# Project_Milestone04.net
KiCad netlist of a schematic drawn in EAGLE
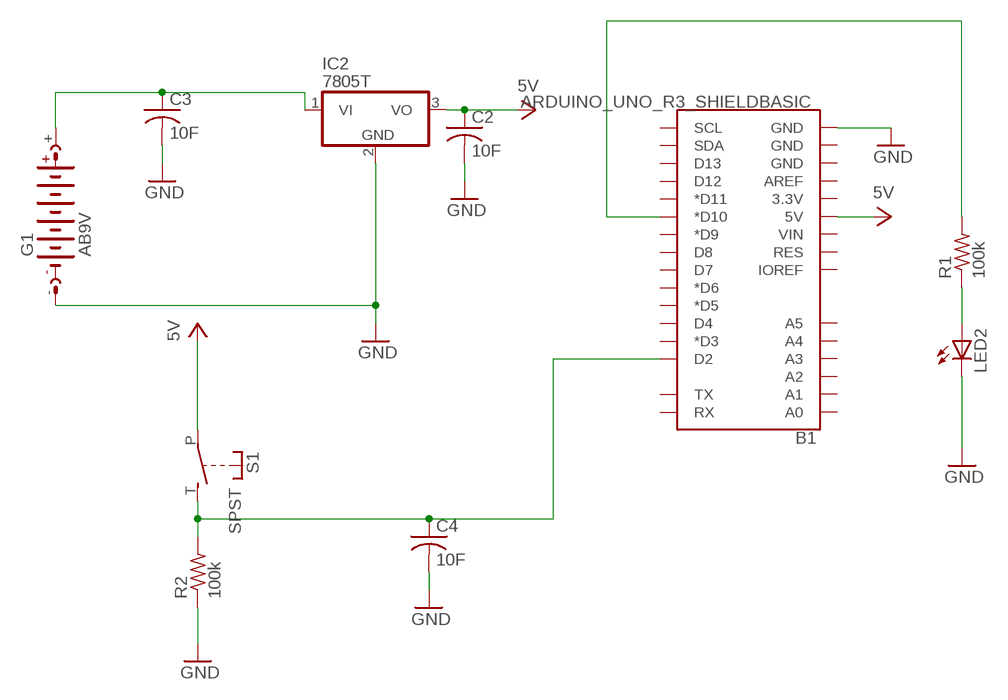
[diagram p0: schematic, sheet 1]

(export (version "E")
  (design (tool "Eeschema 10.0.6"))
  (components
    (comp (ref "B1")
      (value "ARDUINO_UNO_R3_SHIELDBASIC")
      (footprint "eagle-import:UNO_R3_SHIELD")
      (libsource (lib "eagle-import") (part "ARDUINO_UNO_R3_SHIELDBASIC"))
    )
    (comp (ref "C2")
      (value "10F")
      (footprint "eagle-import:C0805")
      (libsource (lib "eagle-import") (part "C-USC0805"))
    )
    (comp (ref "C3")
      (value "10F")
      (footprint "eagle-import:C0805")
      (libsource (lib "eagle-import") (part "C-USC0805"))
    )
    (comp (ref "C4")
      (value "10F")
      (footprint "eagle-import:C0805")
      (libsource (lib "eagle-import") (part "C-USC0805"))
    )
    (comp (ref "G1")
      (value "AB9V")
      (footprint "eagle-import:AB9V")
      (libsource (lib "eagle-import") (part "AB9V"))
    )
    (comp (ref "IC2")
      (value "7805T")
      (footprint "eagle-import:TO220H")
      (libsource (lib "eagle-import") (part "78T05"))
    )
    (comp (ref "LED2")
      (value "LED5MM")
      (footprint "eagle-import:LED5MM")
      (libsource (lib "eagle-import") (part "LED5MM"))
    )
    (comp (ref "R1")
      (value "100k")
      (footprint "eagle-import:0207_10")
      (libsource (lib "eagle-import") (part "R-US_0207/10"))
    )
    (comp (ref "R2")
      (value "100k")
      (footprint "eagle-import:0207_10")
      (libsource (lib "eagle-import") (part "R-US_0207/10"))
    )
    (comp (ref "S1")
      (value "SPST")
      (footprint "eagle-import:JUDCOSPST")
      (libsource (lib "eagle-import") (part "SPST"))
    )
  )
  (nets
    (net (code "1") (name "5V") (class "Default")
      (node (ref "B1") (pin "5V") (pinfunction "5V_5V") (pintype "bidirectional"))
      (node (ref "C2") (pin "1") (pinfunction "1_1") (pintype "passive"))
      (node (ref "IC2") (pin "3") (pinfunction "VO_3") (pintype "passive"))
      (node (ref "S1") (pin "P") (pinfunction "P_P") (pintype "passive"))
    )
    (net (code "2") (name "GND") (class "Default")
      (node (ref "B1") (pin "GND@0") (pinfunction "GND_GND@0") (pintype "bidirectional"))
      (node (ref "C2") (pin "2") (pinfunction "2_2") (pintype "passive"))
      (node (ref "C3") (pin "2") (pinfunction "2_2") (pintype "passive"))
      (node (ref "C4") (pin "2") (pinfunction "2_2") (pintype "passive"))
      (node (ref "G1") (pin "-") (pinfunction "-_-") (pintype "passive"))
      (node (ref "IC2") (pin "2") (pinfunction "GND_2") (pintype "passive"))
      (node (ref "LED2") (pin "K") (pinfunction "C_K") (pintype "passive"))
      (node (ref "R2") (pin "1") (pinfunction "1_1") (pintype "passive"))
    )
    (net (code "3") (name "Net-(B1-*D10)") (class "Default")
      (node (ref "B1") (pin "D10") (pinfunction "*D10_D10") (pintype "bidirectional"))
      (node (ref "R1") (pin "2") (pinfunction "2_2") (pintype "passive"))
    )
    (net (code "4") (name "Net-(IC2-VI)") (class "Default")
      (node (ref "C3") (pin "1") (pinfunction "1_1") (pintype "passive"))
      (node (ref "G1") (pin "+") (pinfunction "+_+") (pintype "passive"))
      (node (ref "IC2") (pin "1") (pinfunction "VI_1") (pintype "input"))
    )
    (net (code "5") (name "Net-(LED2-PadA)") (class "Default")
      (node (ref "LED2") (pin "A") (pinfunction "A_A") (pintype "passive"))
      (node (ref "R1") (pin "1") (pinfunction "1_1") (pintype "passive"))
    )
    (net (code "6") (name "Net-(S1-S)") (class "Default")
      (node (ref "B1") (pin "D2") (pinfunction "D2_D2") (pintype "bidirectional"))
      (node (ref "C4") (pin "1") (pinfunction "1_1") (pintype "passive"))
      (node (ref "R2") (pin "2") (pinfunction "2_2") (pintype "passive"))
      (node (ref "S1") (pin "T") (pinfunction "S_T") (pintype "passive"))
    )
    (net (code "7") (name "unconnected-(B1-*D3-PadD3)") (class "Default")
      (node (ref "B1") (pin "D3") (pinfunction "*D3_D3") (pintype "bidirectional"))
    )
    (net (code "8") (name "unconnected-(B1-*D5-PadD5)") (class "Default")
      (node (ref "B1") (pin "D5") (pinfunction "*D5_D5") (pintype "bidirectional"))
    )
    (net (code "9") (name "unconnected-(B1-*D6-PadD6)") (class "Default")
      (node (ref "B1") (pin "D6") (pinfunction "*D6_D6") (pintype "bidirectional"))
    )
    (net (code "10") (name "unconnected-(B1-*D9-PadD9)") (class "Default")
      (node (ref "B1") (pin "D9") (pinfunction "*D9_D9") (pintype "bidirectional"))
    )
    (net (code "11") (name "unconnected-(B1-*D11-PadD11)") (class "Default")
      (node (ref "B1") (pin "D11") (pinfunction "*D11_D11") (pintype "bidirectional"))
    )
    (net (code "12") (name "unconnected-(B1-GND-PadGND@1)") (class "Default")
      (node (ref "B1") (pin "GND@1") (pinfunction "GND_GND@1") (pintype "bidirectional"))
    )
    (net (code "13") (name "unconnected-(B1-GND-PadGND@2)") (class "Default")
      (node (ref "B1") (pin "GND@2") (pinfunction "GND_GND@2") (pintype "bidirectional"))
    )
    (net (code "14") (name "unconnected-(B1-Pad3.3V)") (class "Default")
      (node (ref "B1") (pin "3.3V") (pinfunction "3.3V_3.3V") (pintype "bidirectional"))
    )
    (net (code "15") (name "unconnected-(B1-PadA0)") (class "Default")
      (node (ref "B1") (pin "A0") (pinfunction "A0_A0") (pintype "bidirectional"))
    )
    (net (code "16") (name "unconnected-(B1-PadA1)") (class "Default")
      (node (ref "B1") (pin "A1") (pinfunction "A1_A1") (pintype "bidirectional"))
    )
    (net (code "17") (name "unconnected-(B1-PadA2)") (class "Default")
      (node (ref "B1") (pin "A2") (pinfunction "A2_A2") (pintype "bidirectional"))
    )
    (net (code "18") (name "unconnected-(B1-PadA3)") (class "Default")
      (node (ref "B1") (pin "A3") (pinfunction "A3_A3") (pintype "bidirectional"))
    )
    (net (code "19") (name "unconnected-(B1-PadA4)") (class "Default")
      (node (ref "B1") (pin "A4") (pinfunction "A4_A4") (pintype "bidirectional"))
    )
    (net (code "20") (name "unconnected-(B1-PadA5)") (class "Default")
      (node (ref "B1") (pin "A5") (pinfunction "A5_A5") (pintype "bidirectional"))
    )
    (net (code "21") (name "unconnected-(B1-PadAREF)") (class "Default")
      (node (ref "B1") (pin "AREF") (pinfunction "AREF_AREF") (pintype "bidirectional"))
    )
    (net (code "22") (name "unconnected-(B1-PadD4)") (class "Default")
      (node (ref "B1") (pin "D4") (pinfunction "D4_D4") (pintype "bidirectional"))
    )
    (net (code "23") (name "unconnected-(B1-PadD7)") (class "Default")
      (node (ref "B1") (pin "D7") (pinfunction "D7_D7") (pintype "bidirectional"))
    )
    (net (code "24") (name "unconnected-(B1-PadD8)") (class "Default")
      (node (ref "B1") (pin "D8") (pinfunction "D8_D8") (pintype "bidirectional"))
    )
    (net (code "25") (name "unconnected-(B1-PadD12)") (class "Default")
      (node (ref "B1") (pin "D12") (pinfunction "D12_D12") (pintype "bidirectional"))
    )
    (net (code "26") (name "unconnected-(B1-PadD13)") (class "Default")
      (node (ref "B1") (pin "D13") (pinfunction "D13_D13") (pintype "bidirectional"))
    )
    (net (code "27") (name "unconnected-(B1-PadIOREF)") (class "Default")
      (node (ref "B1") (pin "IOREF") (pinfunction "IOREF_IOREF") (pintype "bidirectional"))
    )
    (net (code "28") (name "unconnected-(B1-PadRES)") (class "Default")
      (node (ref "B1") (pin "RES") (pinfunction "RES_RES") (pintype "bidirectional"))
    )
    (net (code "29") (name "unconnected-(B1-PadRX)") (class "Default")
      (node (ref "B1") (pin "RX") (pinfunction "RX_RX") (pintype "bidirectional"))
    )
    (net (code "30") (name "unconnected-(B1-PadSCL)") (class "Default")
      (node (ref "B1") (pin "SCL") (pinfunction "SCL_SCL") (pintype "bidirectional"))
    )
    (net (code "31") (name "unconnected-(B1-PadSDA)") (class "Default")
      (node (ref "B1") (pin "SDA") (pinfunction "SDA_SDA") (pintype "bidirectional"))
    )
    (net (code "32") (name "unconnected-(B1-PadTX)") (class "Default")
      (node (ref "B1") (pin "TX") (pinfunction "TX_TX") (pintype "bidirectional"))
    )
    (net (code "33") (name "unconnected-(B1-PadVIN)") (class "Default")
      (node (ref "B1") (pin "VIN") (pinfunction "VIN_VIN") (pintype "bidirectional"))
    )
  )
)
